# Cell_Balancing.net
KiCad netlist of a schematic drawn in Altium Designer
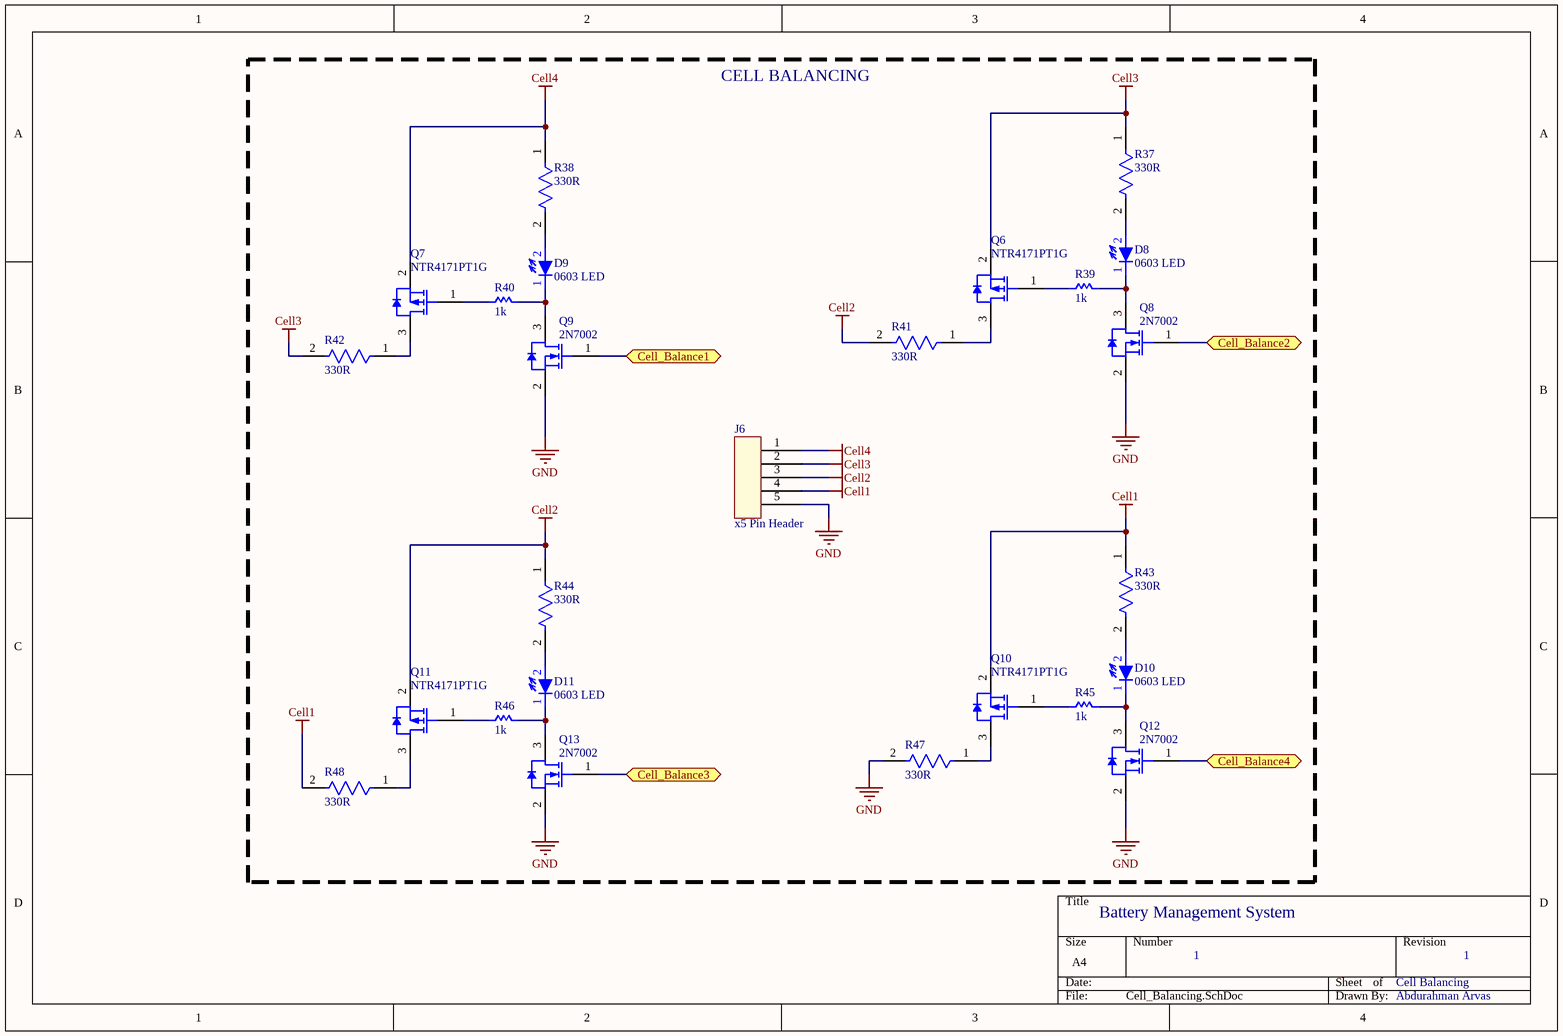
[diagram p0: Cell_Balancing.SchDoc]

(export (version "E")
  (design (tool "Eeschema 10.0.6"))
  (components
    (comp (ref "D8")
      (value "0603 LED")
      (footprint "LED_0603")
      (description "Light Emitting Diode with 0603 footprint.")
      (libsource (lib "Arvas_AltiumSCH") (part "Led 0603"))
    )
    (comp (ref "D9")
      (value "0603 LED")
      (footprint "LED_0603")
      (description "Light Emitting Diode with 0603 footprint.")
      (libsource (lib "Arvas_AltiumSCH") (part "Led 0603"))
    )
    (comp (ref "D10")
      (value "0603 LED")
      (footprint "LED_0603")
      (description "Light Emitting Diode with 0603 footprint.")
      (libsource (lib "Arvas_AltiumSCH") (part "Led 0603"))
    )
    (comp (ref "D11")
      (value "0603 LED")
      (footprint "LED_0603")
      (description "Light Emitting Diode with 0603 footprint.")
      (libsource (lib "Arvas_AltiumSCH") (part "Led 0603"))
    )
    (comp (ref "J6")
      (value "x5 Pin Header")
      (footprint "CONN X5")
      (libsource (lib "Arvas_AltiumSCH") (part "CONN X5"))
    )
    (comp (ref "Q6")
      (value "NTR4171PT1G")
      (footprint "ONSC-SOT-23-3-318-08_V")
      (description "Power MOSFET, -30 V, 3.5 A, Single P-Channel, 3-Pin SOT-23, Pb-Free, Tape and Reel")
      (fields (field (name "MANUFACTURER") "On Semiconductor"))
      (libsource (lib "Altium Content Vault") (part "ONSC-PMOS-G1S2D3-3_D"))
    )
    (comp (ref "Q7")
      (value "NTR4171PT1G")
      (footprint "ONSC-SOT-23-3-318-08_V")
      (description "Power MOSFET, -30 V, 3.5 A, Single P-Channel, 3-Pin SOT-23, Pb-Free, Tape and Reel")
      (fields (field (name "MANUFACTURER") "On Semiconductor"))
      (libsource (lib "Altium Content Vault") (part "ONSC-PMOS-G1S2D3-3_D"))
    )
    (comp (ref "Q8")
      (value "2N7002")
      (footprint "STM-SOT-23-3_V")
      (description "N-channel 60 V, 1.8 Ohm, 0.35 A STripFET(TM) II Power MOSFET, SOT23")
      (fields (field (name "MANUFACTURER") "STMicroelectronics"))
      (libsource (lib "Altium Content Vault") (part "STM-NEMOS-G1S2D3-3"))
    )
    (comp (ref "Q9")
      (value "2N7002")
      (footprint "STM-SOT-23-3_V")
      (description "N-channel 60 V, 1.8 Ohm, 0.35 A STripFET(TM) II Power MOSFET, SOT23")
      (fields (field (name "MANUFACTURER") "STMicroelectronics"))
      (libsource (lib "Altium Content Vault") (part "STM-NEMOS-G1S2D3-3"))
    )
    (comp (ref "Q10")
      (value "NTR4171PT1G")
      (footprint "ONSC-SOT-23-3-318-08_V")
      (description "Power MOSFET, -30 V, 3.5 A, Single P-Channel, 3-Pin SOT-23, Pb-Free, Tape and Reel")
      (fields (field (name "MANUFACTURER") "On Semiconductor"))
      (libsource (lib "Altium Content Vault") (part "ONSC-PMOS-G1S2D3-3_D"))
    )
    (comp (ref "Q11")
      (value "NTR4171PT1G")
      (footprint "ONSC-SOT-23-3-318-08_V")
      (description "Power MOSFET, -30 V, 3.5 A, Single P-Channel, 3-Pin SOT-23, Pb-Free, Tape and Reel")
      (fields (field (name "MANUFACTURER") "On Semiconductor"))
      (libsource (lib "Altium Content Vault") (part "ONSC-PMOS-G1S2D3-3_D"))
    )
    (comp (ref "Q12")
      (value "2N7002")
      (footprint "STM-SOT-23-3_V")
      (description "N-channel 60 V, 1.8 Ohm, 0.35 A STripFET(TM) II Power MOSFET, SOT23")
      (fields (field (name "MANUFACTURER") "STMicroelectronics"))
      (libsource (lib "Altium Content Vault") (part "STM-NEMOS-G1S2D3-3"))
    )
    (comp (ref "Q13")
      (value "2N7002")
      (footprint "STM-SOT-23-3_V")
      (description "N-channel 60 V, 1.8 Ohm, 0.35 A STripFET(TM) II Power MOSFET, SOT23")
      (fields (field (name "MANUFACTURER") "STMicroelectronics"))
      (libsource (lib "Altium Content Vault") (part "STM-NEMOS-G1S2D3-3"))
    )
    (comp (ref "R37")
      (value "330R")
      (footprint "FP-CRCW2512-e3-IPC_B")
      (description "RES Thick Film, 330Ω, 5%, 1W, 200ppm/°C, 2512")
      (fields (field (name "TOLERANCE") "5%"))
      (libsource (lib "Altium Content Vault") (part "1029c3af85768c4190bb7ad29bc67b5"))
    )
    (comp (ref "R38")
      (value "330R")
      (footprint "FP-CRCW2512-e3-IPC_B")
      (description "RES Thick Film, 330Ω, 5%, 1W, 200ppm/°C, 2512")
      (fields (field (name "TOLERANCE") "5%"))
      (libsource (lib "Altium Content Vault") (part "1029c3af85768c4190bb7ad29bc67b5"))
    )
    (comp (ref "R39")
      (value "1k")
      (footprint "R0805")
      (description "SMD Chip Resistor")
      (libsource (lib "Arvas_AltiumSCH") (part "SMD Resistor"))
    )
    (comp (ref "R40")
      (value "1k")
      (footprint "R0805")
      (description "SMD Chip Resistor")
      (libsource (lib "Arvas_AltiumSCH") (part "SMD Resistor"))
    )
    (comp (ref "R41")
      (value "330R")
      (footprint "FP-CRCW2512-e3-IPC_B")
      (description "RES Thick Film, 330Ω, 5%, 1W, 200ppm/°C, 2512")
      (fields (field (name "TOLERANCE") "5%"))
      (libsource (lib "Altium Content Vault") (part "1029c3af85768c4190bb7ad29bc67b5"))
    )
    (comp (ref "R42")
      (value "330R")
      (footprint "FP-CRCW2512-e3-IPC_B")
      (description "RES Thick Film, 330Ω, 5%, 1W, 200ppm/°C, 2512")
      (fields (field (name "TOLERANCE") "5%"))
      (libsource (lib "Altium Content Vault") (part "1029c3af85768c4190bb7ad29bc67b5"))
    )
    (comp (ref "R43")
      (value "330R")
      (footprint "FP-CRCW2512-e3-IPC_B")
      (description "RES Thick Film, 330Ω, 5%, 1W, 200ppm/°C, 2512")
      (fields (field (name "TOLERANCE") "5%"))
      (libsource (lib "Altium Content Vault") (part "1029c3af85768c4190bb7ad29bc67b5"))
    )
    (comp (ref "R44")
      (value "330R")
      (footprint "FP-CRCW2512-e3-IPC_B")
      (description "RES Thick Film, 330Ω, 5%, 1W, 200ppm/°C, 2512")
      (fields (field (name "TOLERANCE") "5%"))
      (libsource (lib "Altium Content Vault") (part "1029c3af85768c4190bb7ad29bc67b5"))
    )
    (comp (ref "R45")
      (value "1k")
      (footprint "R0805")
      (description "SMD Chip Resistor")
      (libsource (lib "Arvas_AltiumSCH") (part "SMD Resistor"))
    )
    (comp (ref "R46")
      (value "1k")
      (footprint "R0805")
      (description "SMD Chip Resistor")
      (libsource (lib "Arvas_AltiumSCH") (part "SMD Resistor"))
    )
    (comp (ref "R47")
      (value "330R")
      (footprint "FP-CRCW2512-e3-IPC_B")
      (description "RES Thick Film, 330Ω, 5%, 1W, 200ppm/°C, 2512")
      (fields (field (name "TOLERANCE") "5%"))
      (libsource (lib "Altium Content Vault") (part "1029c3af85768c4190bb7ad29bc67b5"))
    )
    (comp (ref "R48")
      (value "330R")
      (footprint "FP-CRCW2512-e3-IPC_B")
      (description "RES Thick Film, 330Ω, 5%, 1W, 200ppm/°C, 2512")
      (fields (field (name "TOLERANCE") "5%"))
      (libsource (lib "Altium Content Vault") (part "1029c3af85768c4190bb7ad29bc67b5"))
    )
  )
  (nets
    (net (code "1") (name "/Cell_Balance1") (class "Default")
      (node (ref "Q9") (pin "1") (pinfunction "G_1") (pintype "passive"))
    )
    (net (code "2") (name "/Cell_Balance2") (class "Default")
      (node (ref "Q8") (pin "1") (pinfunction "G_1") (pintype "passive"))
    )
    (net (code "3") (name "/Cell_Balance3") (class "Default")
      (node (ref "Q13") (pin "1") (pinfunction "G_1") (pintype "passive"))
    )
    (net (code "4") (name "/Cell_Balance4") (class "Default")
      (node (ref "Q12") (pin "1") (pinfunction "G_1") (pintype "passive"))
    )
    (net (code "5") (name "Cell1") (class "Default")
      (node (ref "J6") (pin "4") (pinfunction "4_4") (pintype "passive"))
      (node (ref "Q10") (pin "2") (pinfunction "S_2") (pintype "passive"))
      (node (ref "R43") (pin "1") (pinfunction "1_1") (pintype "passive"))
      (node (ref "R48") (pin "2") (pinfunction "2_2") (pintype "passive"))
    )
    (net (code "6") (name "Cell2") (class "Default")
      (node (ref "J6") (pin "3") (pinfunction "3_3") (pintype "passive"))
      (node (ref "Q11") (pin "2") (pinfunction "S_2") (pintype "passive"))
      (node (ref "R41") (pin "2") (pinfunction "2_2") (pintype "passive"))
      (node (ref "R44") (pin "1") (pinfunction "1_1") (pintype "passive"))
    )
    (net (code "7") (name "Cell3") (class "Default")
      (node (ref "J6") (pin "2") (pinfunction "2_2") (pintype "passive"))
      (node (ref "Q6") (pin "2") (pinfunction "S_2") (pintype "passive"))
      (node (ref "R37") (pin "1") (pinfunction "1_1") (pintype "passive"))
      (node (ref "R42") (pin "2") (pinfunction "2_2") (pintype "passive"))
    )
    (net (code "8") (name "Cell4") (class "Default")
      (node (ref "J6") (pin "1") (pinfunction "1_1") (pintype "passive"))
      (node (ref "Q7") (pin "2") (pinfunction "S_2") (pintype "passive"))
      (node (ref "R38") (pin "1") (pinfunction "1_1") (pintype "passive"))
    )
    (net (code "9") (name "GND") (class "Default")
      (node (ref "J6") (pin "5") (pinfunction "5_5") (pintype "passive"))
      (node (ref "Q12") (pin "2") (pinfunction "S_2") (pintype "passive"))
      (node (ref "Q13") (pin "2") (pinfunction "S_2") (pintype "passive"))
      (node (ref "Q8") (pin "2") (pinfunction "S_2") (pintype "passive"))
      (node (ref "Q9") (pin "2") (pinfunction "S_2") (pintype "passive"))
      (node (ref "R47") (pin "2") (pinfunction "2_2") (pintype "passive"))
    )
    (net (code "10") (name "Net-(D8-Anode)") (class "Default")
      (node (ref "D8") (pin "2") (pinfunction "Anode_2") (pintype "passive"))
      (node (ref "R37") (pin "2") (pinfunction "2_2") (pintype "passive"))
    )
    (net (code "11") (name "Net-(D8-Cathode)") (class "Default")
      (node (ref "D8") (pin "1") (pinfunction "Cathode_1") (pintype "passive"))
      (node (ref "Q8") (pin "3") (pinfunction "D_3") (pintype "passive"))
      (node (ref "R39") (pin "2") (pinfunction "2_2") (pintype "passive"))
    )
    (net (code "12") (name "Net-(D9-Anode)") (class "Default")
      (node (ref "D9") (pin "2") (pinfunction "Anode_2") (pintype "passive"))
      (node (ref "R38") (pin "2") (pinfunction "2_2") (pintype "passive"))
    )
    (net (code "13") (name "Net-(D9-Cathode)") (class "Default")
      (node (ref "D9") (pin "1") (pinfunction "Cathode_1") (pintype "passive"))
      (node (ref "Q9") (pin "3") (pinfunction "D_3") (pintype "passive"))
      (node (ref "R40") (pin "2") (pinfunction "2_2") (pintype "passive"))
    )
    (net (code "14") (name "Net-(D10-Anode)") (class "Default")
      (node (ref "D10") (pin "2") (pinfunction "Anode_2") (pintype "passive"))
      (node (ref "R43") (pin "2") (pinfunction "2_2") (pintype "passive"))
    )
    (net (code "15") (name "Net-(D10-Cathode)") (class "Default")
      (node (ref "D10") (pin "1") (pinfunction "Cathode_1") (pintype "passive"))
      (node (ref "Q12") (pin "3") (pinfunction "D_3") (pintype "passive"))
      (node (ref "R45") (pin "2") (pinfunction "2_2") (pintype "passive"))
    )
    (net (code "16") (name "Net-(D11-Anode)") (class "Default")
      (node (ref "D11") (pin "2") (pinfunction "Anode_2") (pintype "passive"))
      (node (ref "R44") (pin "2") (pinfunction "2_2") (pintype "passive"))
    )
    (net (code "17") (name "Net-(D11-Cathode)") (class "Default")
      (node (ref "D11") (pin "1") (pinfunction "Cathode_1") (pintype "passive"))
      (node (ref "Q13") (pin "3") (pinfunction "D_3") (pintype "passive"))
      (node (ref "R46") (pin "2") (pinfunction "2_2") (pintype "passive"))
    )
    (net (code "18") (name "Net-(Q6-D)") (class "Default")
      (node (ref "Q6") (pin "3") (pinfunction "D_3") (pintype "passive"))
      (node (ref "R41") (pin "1") (pinfunction "1_1") (pintype "passive"))
    )
    (net (code "19") (name "Net-(Q6-G)") (class "Default")
      (node (ref "Q6") (pin "1") (pinfunction "G_1") (pintype "passive"))
      (node (ref "R39") (pin "1") (pinfunction "1_1") (pintype "passive"))
    )
    (net (code "20") (name "Net-(Q7-D)") (class "Default")
      (node (ref "Q7") (pin "3") (pinfunction "D_3") (pintype "passive"))
      (node (ref "R42") (pin "1") (pinfunction "1_1") (pintype "passive"))
    )
    (net (code "21") (name "Net-(Q7-G)") (class "Default")
      (node (ref "Q7") (pin "1") (pinfunction "G_1") (pintype "passive"))
      (node (ref "R40") (pin "1") (pinfunction "1_1") (pintype "passive"))
    )
    (net (code "22") (name "Net-(Q10-D)") (class "Default")
      (node (ref "Q10") (pin "3") (pinfunction "D_3") (pintype "passive"))
      (node (ref "R47") (pin "1") (pinfunction "1_1") (pintype "passive"))
    )
    (net (code "23") (name "Net-(Q10-G)") (class "Default")
      (node (ref "Q10") (pin "1") (pinfunction "G_1") (pintype "passive"))
      (node (ref "R45") (pin "1") (pinfunction "1_1") (pintype "passive"))
    )
    (net (code "24") (name "Net-(Q11-D)") (class "Default")
      (node (ref "Q11") (pin "3") (pinfunction "D_3") (pintype "passive"))
      (node (ref "R48") (pin "1") (pinfunction "1_1") (pintype "passive"))
    )
    (net (code "25") (name "Net-(Q11-G)") (class "Default")
      (node (ref "Q11") (pin "1") (pinfunction "G_1") (pintype "passive"))
      (node (ref "R46") (pin "1") (pinfunction "1_1") (pintype "passive"))
    )
  )
)
